# mag_encoder_Rev1.net
KiCad netlist of a schematic drawn in EAGLE
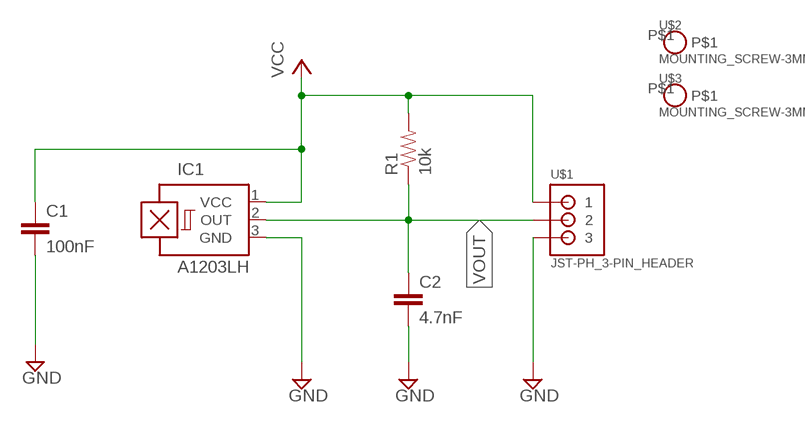
[diagram p0: schematic, sheet 1]

(export (version "E")
  (design (tool "Eeschema 10.0.6"))
  (components
    (comp (ref "C1")
      (value "100nF")
      (footprint "eagle-import:0603-CAP")
      (libsource (lib "eagle-import") (part "CAP0603-CAP"))
    )
    (comp (ref "C2")
      (value "4.7nF")
      (footprint "eagle-import:0603-CAP")
      (libsource (lib "eagle-import") (part "4.7NF-50V-10%(0603)"))
    )
    (comp (ref "IC1")
      (value "A1203LH")
      (footprint "eagle-import:SOT23-W")
      (fields (field (name "MF") "ALLEGRO MICROSYSTEMS, INC.") (field (name "MPN") "A1203LLHLT-T"))
      (libsource (lib "eagle-import") (part "A12?LH03"))
    )
    (comp (ref "R1")
      (value "10k")
      (footprint "eagle-import:0603")
      (libsource (lib "eagle-import") (part "10.5KOHM1/10W1%(0603)"))
    )
    (comp (ref "U$1")
      (value "JST-PH_3-PIN_HEADER")
      (footprint "eagle-import:JST_B3B-PH_HEADER")
      (libsource (lib "eagle-import") (part "JST-PH_3-PIN_HEADER"))
    )
    (comp (ref "U$2")
      (value "MOUNTING_SCREW-3MM")
      (footprint "eagle-import:MOUNTING_SCREW-3MM")
      (libsource (lib "eagle-import") (part "MOUNTING_SCREW-3MM"))
    )
    (comp (ref "U$3")
      (value "MOUNTING_SCREW-3MM")
      (footprint "eagle-import:MOUNTING_SCREW-3MM")
      (libsource (lib "eagle-import") (part "MOUNTING_SCREW-3MM"))
    )
  )
  (nets
    (net (code "1") (name "GND") (class "Default")
      (node (ref "C1") (pin "2") (pinfunction "2_2") (pintype "passive"))
      (node (ref "C2") (pin "2") (pinfunction "2_2") (pintype "passive"))
      (node (ref "IC1") (pin "3") (pinfunction "GND_3") (pintype "power_in"))
      (node (ref "U$1") (pin "P3") (pinfunction "3_P3") (pintype "bidirectional"))
    )
    (net (code "2") (name "VCC") (class "Default")
      (node (ref "C1") (pin "1") (pinfunction "1_1") (pintype "passive"))
      (node (ref "IC1") (pin "1") (pinfunction "VCC_1") (pintype "power_in"))
      (node (ref "R1") (pin "2") (pinfunction "2_2") (pintype "passive"))
      (node (ref "U$1") (pin "P1") (pinfunction "1_P1") (pintype "bidirectional"))
    )
    (net (code "3") (name "VOUT") (class "Default")
      (node (ref "C2") (pin "1") (pinfunction "1_1") (pintype "passive"))
      (node (ref "IC1") (pin "2") (pinfunction "OUT_2") (pintype "output"))
      (node (ref "R1") (pin "1") (pinfunction "1_1") (pintype "passive"))
      (node (ref "U$1") (pin "P2") (pinfunction "2_P2") (pintype "bidirectional"))
    )
    (net (code "4") (name "unconnected-(U$2-PadP$1)") (class "Default")
      (node (ref "U$2") (pin "P$1") (pinfunction "P$1_P$1") (pintype "bidirectional"))
    )
    (net (code "5") (name "unconnected-(U$3-PadP$1)") (class "Default")
      (node (ref "U$3") (pin "P$1") (pinfunction "P$1_P$1") (pintype "bidirectional"))
    )
  )
)
